# Offboard.net
KiCad netlist of a schematic drawn in Altium Designer
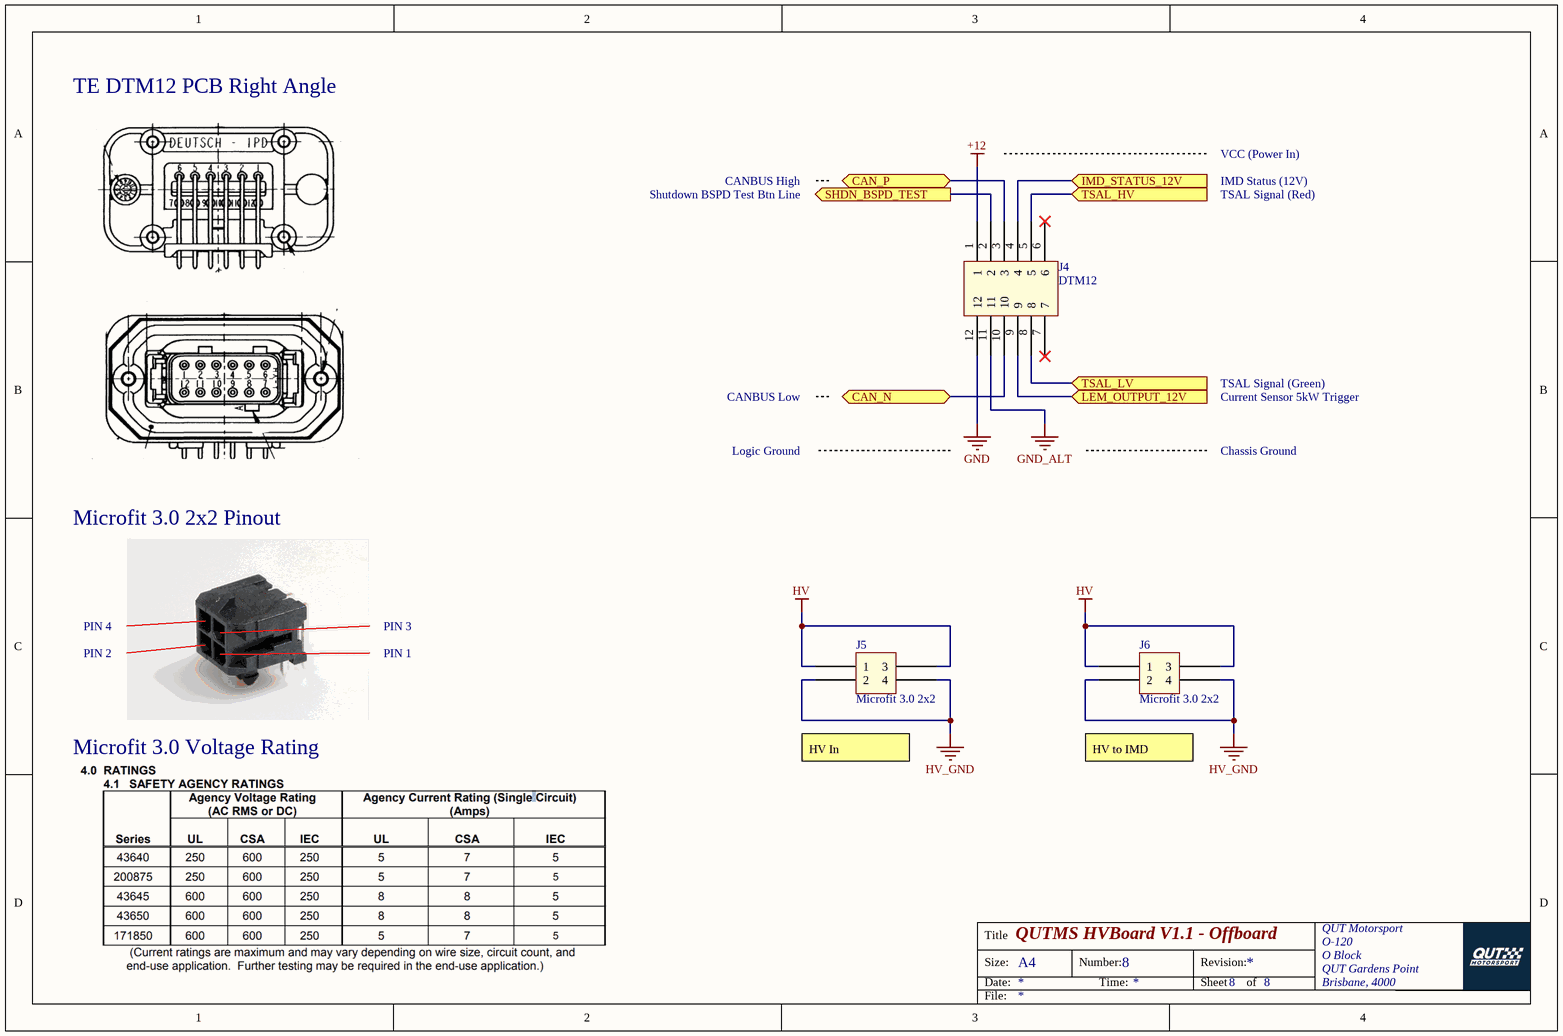
[diagram p0: Offboard.SchDoc]

(export (version "E")
  (design (tool "Eeschema 10.0.6"))
  (components
    (comp (ref "J4")
      (value "DTM12")
      (footprint "DTM13-12PA")
      (libsource (lib "QUTMS_DeutschPCB") (part "DTM12"))
    )
    (comp (ref "J5")
      (value "Microfit 3.0 2x2")
      (footprint "Microfit_2X2_R_TH")
      (libsource (lib "QUTMS_Microfit") (part "Microfit_2x2"))
    )
    (comp (ref "J6")
      (value "Microfit 3.0 2x2")
      (footprint "Microfit_2X2_R_TH")
      (libsource (lib "QUTMS_Microfit") (part "Microfit_2x2"))
    )
  )
  (nets
    (net (code "1") (name "+12") (class "Default")
      (node (ref "J4") (pin "1") (pinfunction "1_1") (pintype "passive"))
    )
    (net (code "2") (name "/CAN_N") (class "Default")
      (node (ref "J4") (pin "10") (pinfunction "10_10") (pintype "passive"))
    )
    (net (code "3") (name "/CAN_P") (class "Default")
      (node (ref "J4") (pin "3") (pinfunction "3_3") (pintype "passive"))
    )
    (net (code "4") (name "/IMD_STATUS_12V") (class "Default")
      (node (ref "J4") (pin "4") (pinfunction "4_4") (pintype "passive"))
    )
    (net (code "5") (name "/LEM_OUTPUT_12V") (class "Default")
      (node (ref "J4") (pin "9") (pinfunction "9_9") (pintype "passive"))
    )
    (net (code "6") (name "/SHDN_BSPD_TEST") (class "Default")
      (node (ref "J4") (pin "2") (pinfunction "2_2") (pintype "passive"))
    )
    (net (code "7") (name "/TSAL_HV") (class "Default")
      (node (ref "J4") (pin "5") (pinfunction "5_5") (pintype "passive"))
    )
    (net (code "8") (name "/TSAL_LV") (class "Default")
      (node (ref "J4") (pin "8") (pinfunction "8_8") (pintype "passive"))
    )
    (net (code "9") (name "GND") (class "Default")
      (node (ref "J4") (pin "12") (pinfunction "12_12") (pintype "passive"))
    )
    (net (code "10") (name "GND_ALT") (class "Default")
      (node (ref "J4") (pin "11") (pinfunction "11_11") (pintype "passive"))
    )
    (net (code "11") (name "HV") (class "Default")
      (node (ref "J5") (pin "1") (pinfunction "1_1") (pintype "passive"))
      (node (ref "J5") (pin "3") (pinfunction "3_3") (pintype "passive"))
      (node (ref "J6") (pin "1") (pinfunction "1_1") (pintype "passive"))
      (node (ref "J6") (pin "3") (pinfunction "3_3") (pintype "passive"))
    )
    (net (code "12") (name "HV_GND") (class "Default")
      (node (ref "J5") (pin "2") (pinfunction "2_2") (pintype "passive"))
      (node (ref "J5") (pin "4") (pinfunction "4_4") (pintype "passive"))
      (node (ref "J6") (pin "2") (pinfunction "2_2") (pintype "passive"))
      (node (ref "J6") (pin "4") (pinfunction "4_4") (pintype "passive"))
    )
    (net (code "13") (name "unconnected-(J4-Pad6)") (class "Default")
      (node (ref "J4") (pin "6") (pinfunction "6_6") (pintype "passive+no_connect"))
    )
    (net (code "14") (name "unconnected-(J4-Pad7)") (class "Default")
      (node (ref "J4") (pin "7") (pinfunction "7_7") (pintype "passive+no_connect"))
    )
  )
)
